# OpAmpISet.net
KiCad netlist of a schematic drawn in Altium Designer
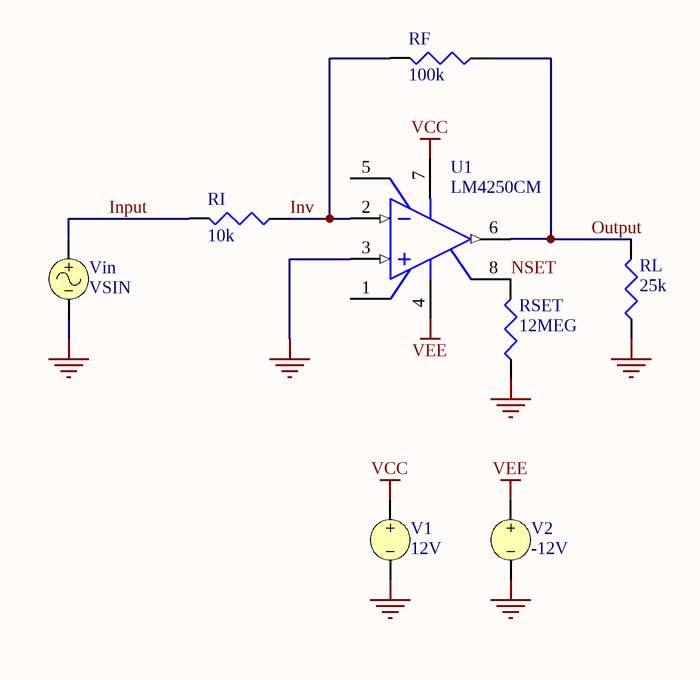
[diagram p0: OpAmpISet.schdoc]

(export (version "E")
  (design (tool "Eeschema 10.0.6"))
  (components
    (comp (ref "RF") (value "100k") (description "Resistor") (libsource (lib "*") (part "RES")))
    (comp (ref "RI") (value "10k") (description "Resistor") (libsource (lib "*") (part "RES")))
    (comp (ref "RL") (value "25k") (description "Resistor") (libsource (lib "") (part "RES_1")))
    (comp (ref "RSET")
      (value "12MEG")
      (description "Resistor")
      (fields (field (name "Comment") "25k"))
      (libsource (lib "") (part "RES_1"))
    )
    (comp (ref "U1")
      (value "LM4250CM")
      (footprint "M08A_N")
      (description "Programmable Operational Amplifier")
      (fields
        (field (name "MANUFACTURER") "National Semiconductor")
        (field (name "DIGIKEYPARTNUMBER") "LM4250CM-ND")
        (field (name "PUBLISHER") "Altium Limited")
      )
      (libsource (lib "NSC Amplifier with SIM models") (part "LM4250CM"))
    )
    (comp (ref "V1") (value "12V") (description "Voltage Source") (libsource (lib "*") (part "VSRC")))
    (comp (ref "V2") (value "-12V") (description "Voltage Source") (libsource (lib "*") (part "VSRC")))
    (comp (ref "Vin")
      (value "VSIN")
      (description "Sinusoidal Voltage Source")
      (libsource (lib "*") (part "VSIN"))
    )
  )
  (nets
    (net (code "1") (name "/Input") (class "Default")
      (node (ref "RI") (pin "1") (pinfunction "TOP_1") (pintype "passive"))
      (node (ref "Vin") (pin "1") (pinfunction "1_1") (pintype "passive"))
    )
    (net (code "2") (name "/Inv") (class "Default")
      (node (ref "RF") (pin "1") (pinfunction "TOP_1") (pintype "passive"))
      (node (ref "RI") (pin "2") (pinfunction "BOT_2") (pintype "passive"))
      (node (ref "U1") (pin "2") (pinfunction "IN-_2") (pintype "input"))
    )
    (net (code "3") (name "/NSET") (class "Default")
      (node (ref "RSET") (pin "1") (pinfunction "TOP_1") (pintype "passive"))
      (node (ref "U1") (pin "8") (pinfunction "I_SET_8") (pintype "passive"))
    )
    (net (code "4") (name "/Output") (class "Default")
      (node (ref "RF") (pin "2") (pinfunction "BOT_2") (pintype "passive"))
      (node (ref "RL") (pin "1") (pinfunction "TOP_1") (pintype "passive"))
      (node (ref "U1") (pin "6") (pinfunction "OUT_6") (pintype "output"))
    )
    (net (code "5") (name "GND") (class "Default")
      (node (ref "RL") (pin "2") (pinfunction "BOT_2") (pintype "passive"))
      (node (ref "RSET") (pin "2") (pinfunction "BOT_2") (pintype "passive"))
      (node (ref "U1") (pin "3") (pinfunction "IN+_3") (pintype "input"))
      (node (ref "V1") (pin "2") (pinfunction "2_2") (pintype "passive"))
      (node (ref "V2") (pin "2") (pinfunction "2_2") (pintype "passive"))
      (node (ref "Vin") (pin "2") (pinfunction "2_2") (pintype "passive"))
    )
    (net (code "6") (name "VCC") (class "Default")
      (node (ref "U1") (pin "7") (pinfunction "V+_7") (pintype "power_in"))
      (node (ref "V1") (pin "1") (pinfunction "1_1") (pintype "passive"))
    )
    (net (code "7") (name "VEE") (class "Default")
      (node (ref "U1") (pin "4") (pinfunction "V-_4") (pintype "power_in"))
      (node (ref "V2") (pin "1") (pinfunction "1_1") (pintype "passive"))
    )
    (net (code "8") (name "unconnected-(U1-OFS_NULL-Pad1)") (class "Default")
      (node (ref "U1") (pin "1") (pinfunction "OFS_NULL_1") (pintype "passive"))
    )
    (net (code "9") (name "unconnected-(U1-OFS_NULL-Pad5)") (class "Default")
      (node (ref "U1") (pin "5") (pinfunction "OFS_NULL_5") (pintype "passive"))
    )
  )
)
